# key-board.net
KiCad netlist of a schematic drawn in EAGLE
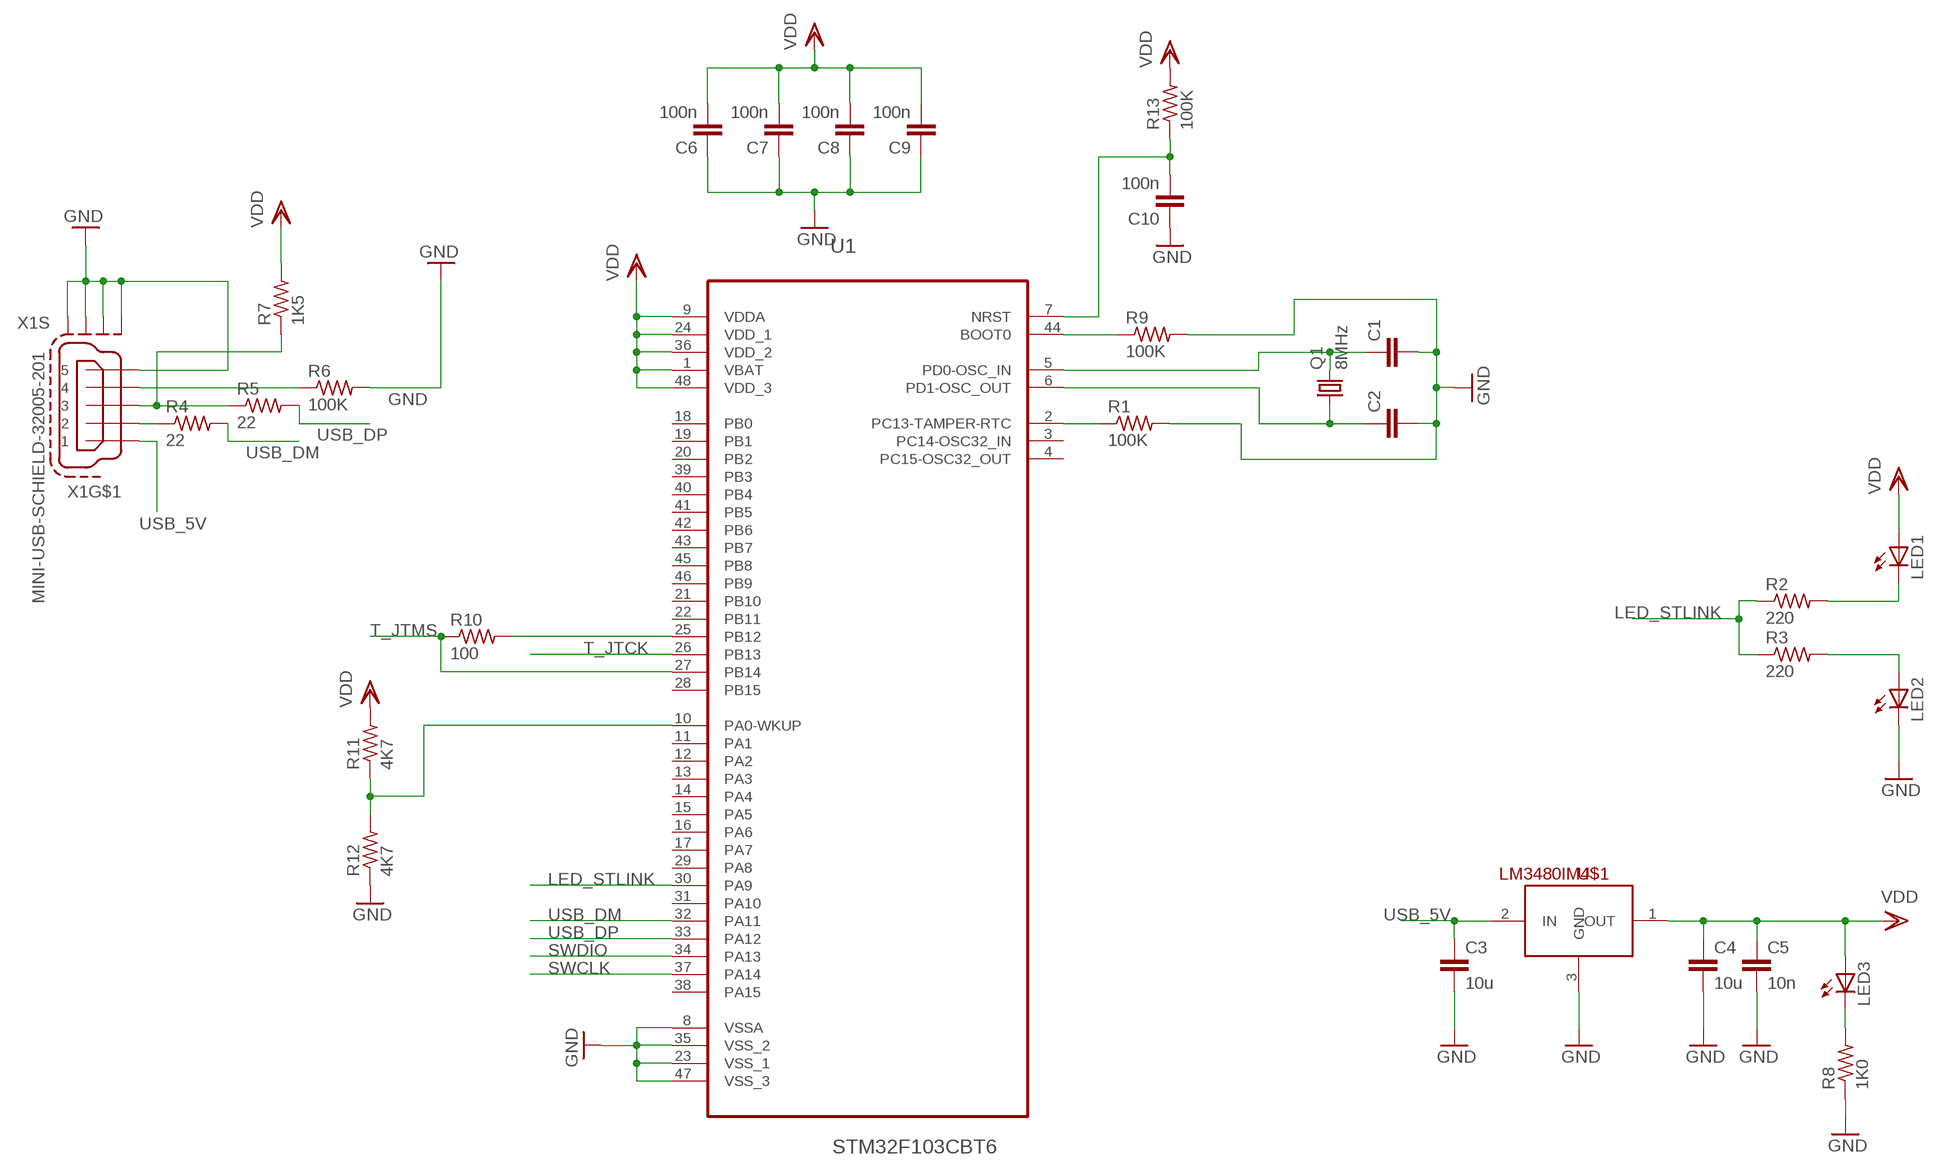
[diagram p0: schematic, sheet 1]

(export (version "E")
  (design (tool "Eeschema 10.0.6"))
  (components
    (comp (ref "C1")
      (value "C-EUC0402")
      (footprint "eagle-import:C0402")
      (libsource (lib "eagle-import") (part "C-EUC0402"))
    )
    (comp (ref "C2")
      (value "C-EUC0402")
      (footprint "eagle-import:C0402")
      (libsource (lib "eagle-import") (part "C-EUC0402"))
    )
    (comp (ref "C3")
      (value "10u")
      (footprint "eagle-import:C0805")
      (libsource (lib "eagle-import") (part "C-EUC0805"))
    )
    (comp (ref "C4")
      (value "10u")
      (footprint "eagle-import:C0805")
      (libsource (lib "eagle-import") (part "C-EUC0805"))
    )
    (comp (ref "C5")
      (value "10n")
      (footprint "eagle-import:C0402")
      (libsource (lib "eagle-import") (part "C-EUC0402"))
    )
    (comp (ref "C6")
      (value "100n")
      (footprint "eagle-import:C0402")
      (libsource (lib "eagle-import") (part "C-EUC0402"))
    )
    (comp (ref "C7")
      (value "100n")
      (footprint "eagle-import:C0402")
      (libsource (lib "eagle-import") (part "C-EUC0402"))
    )
    (comp (ref "C8")
      (value "100n")
      (footprint "eagle-import:C0402")
      (libsource (lib "eagle-import") (part "C-EUC0402"))
    )
    (comp (ref "C9")
      (value "100n")
      (footprint "eagle-import:C0402")
      (libsource (lib "eagle-import") (part "C-EUC0402"))
    )
    (comp (ref "C10")
      (value "100n")
      (footprint "eagle-import:C0402")
      (libsource (lib "eagle-import") (part "C-EUC0402"))
    )
    (comp (ref "LED1")
      (value "LEDCHIPLED-0603-TTW")
      (footprint "eagle-import:CHIPLED-0603-TTW")
      (libsource (lib "eagle-import") (part "LEDCHIPLED-0603-TTW"))
    )
    (comp (ref "LED2")
      (value "LEDCHIPLED-0603-TTW")
      (footprint "eagle-import:CHIPLED-0603-TTW")
      (libsource (lib "eagle-import") (part "LEDCHIPLED-0603-TTW"))
    )
    (comp (ref "LED3")
      (value "LEDCHIPLED-0603-TTW")
      (footprint "eagle-import:CHIPLED-0603-TTW")
      (libsource (lib "eagle-import") (part "LEDCHIPLED-0603-TTW"))
    )
    (comp (ref "Q1")
      (value "8MHz")
      (footprint "eagle-import:HC49U-V")
      (libsource (lib "eagle-import") (part "CRYSTALHC49U-V"))
    )
    (comp (ref "R1")
      (value "100K")
      (footprint "eagle-import:R0402")
      (libsource (lib "eagle-import") (part "R-US_R0402"))
    )
    (comp (ref "R2")
      (value "220")
      (footprint "eagle-import:R0402")
      (libsource (lib "eagle-import") (part "R-US_R0402"))
    )
    (comp (ref "R3")
      (value "220")
      (footprint "eagle-import:R0402")
      (libsource (lib "eagle-import") (part "R-US_R0402"))
    )
    (comp (ref "R4")
      (value "22")
      (footprint "eagle-import:R0402")
      (libsource (lib "eagle-import") (part "R-US_R0402"))
    )
    (comp (ref "R5")
      (value "22")
      (footprint "eagle-import:R0402")
      (libsource (lib "eagle-import") (part "R-US_R0402"))
    )
    (comp (ref "R6")
      (value "100K")
      (footprint "eagle-import:R0402")
      (libsource (lib "eagle-import") (part "R-US_R0402"))
    )
    (comp (ref "R7")
      (value "1K5")
      (footprint "eagle-import:R0402")
      (libsource (lib "eagle-import") (part "R-US_R0402"))
    )
    (comp (ref "R8")
      (value "1K0")
      (footprint "eagle-import:R0402")
      (libsource (lib "eagle-import") (part "R-US_R0402"))
    )
    (comp (ref "R9")
      (value "100K")
      (footprint "eagle-import:R0402")
      (libsource (lib "eagle-import") (part "R-US_R0402"))
    )
    (comp (ref "R10")
      (value "100")
      (footprint "eagle-import:R0402")
      (libsource (lib "eagle-import") (part "R-US_R0402"))
    )
    (comp (ref "R11")
      (value "4K7")
      (footprint "eagle-import:R0402")
      (libsource (lib "eagle-import") (part "R-US_R0402"))
    )
    (comp (ref "R12")
      (value "4K7")
      (footprint "eagle-import:R0402")
      (libsource (lib "eagle-import") (part "R-US_R0402"))
    )
    (comp (ref "R13")
      (value "100K")
      (footprint "eagle-import:R0402")
      (libsource (lib "eagle-import") (part "R-US_R0402"))
    )
    (comp (ref "U$1")
      (value "LM3480IM4")
      (footprint "eagle-import:SOT23-3")
      (libsource (lib "eagle-import") (part "LM3480IM4"))
    )
    (comp (ref "U1")
      (value "STM32F103CBT6")
      (footprint "eagle-import:QFP50P900X900X160-48N")
      (libsource (lib "eagle-import") (part "STM32F103CBT6"))
    )
    (comp (ref "X1")
      (value "MINI-USB-SCHIELD-32005-201")
      (footprint "eagle-import:32005-201")
      (libsource (lib "eagle-import") (part "MINI-USB-SCHIELD-32005-201"))
    )
  )
  (nets
    (net (code "1") (name "/LED_STLINK") (class "Default")
      (node (ref "R2") (pin "1") (pinfunction "1_1") (pintype "passive"))
      (node (ref "R3") (pin "1") (pinfunction "1_1") (pintype "passive"))
      (node (ref "U1") (pin "30") (pinfunction "PA9_30") (pintype "bidirectional"))
    )
    (net (code "2") (name "/SWCLK") (class "Default")
      (node (ref "U1") (pin "37") (pinfunction "PA14_37") (pintype "bidirectional"))
    )
    (net (code "3") (name "/SWDIO") (class "Default")
      (node (ref "U1") (pin "34") (pinfunction "PA13_34") (pintype "bidirectional"))
    )
    (net (code "4") (name "/T_JTCK") (class "Default")
      (node (ref "U1") (pin "26") (pinfunction "PB13_26") (pintype "bidirectional"))
    )
    (net (code "5") (name "/T_JTMS") (class "Default")
      (node (ref "R10") (pin "1") (pinfunction "1_1") (pintype "passive"))
      (node (ref "U1") (pin "27") (pinfunction "PB14_27") (pintype "bidirectional"))
    )
    (net (code "6") (name "/USB_5V") (class "Default")
      (node (ref "C3") (pin "1") (pinfunction "1_1") (pintype "passive"))
      (node (ref "U$1") (pin "2") (pinfunction "IN_2") (pintype "bidirectional"))
      (node (ref "X1") (pin "1") (pinfunction "1_1") (pintype "passive"))
    )
    (net (code "7") (name "/USB_DM") (class "Default")
      (node (ref "R4") (pin "2") (pinfunction "2_2") (pintype "passive"))
      (node (ref "U1") (pin "32") (pinfunction "PA11_32") (pintype "power_in"))
    )
    (net (code "8") (name "/USB_DP") (class "Default")
      (node (ref "R5") (pin "2") (pinfunction "2_2") (pintype "passive"))
      (node (ref "U1") (pin "33") (pinfunction "PA12_33") (pintype "bidirectional"))
    )
    (net (code "9") (name "GND") (class "Default")
      (node (ref "C1") (pin "2") (pinfunction "2_2") (pintype "passive"))
      (node (ref "C10") (pin "1") (pinfunction "1_1") (pintype "passive"))
      (node (ref "C2") (pin "2") (pinfunction "2_2") (pintype "passive"))
      (node (ref "C3") (pin "2") (pinfunction "2_2") (pintype "passive"))
      (node (ref "C4") (pin "2") (pinfunction "2_2") (pintype "passive"))
      (node (ref "C5") (pin "2") (pinfunction "2_2") (pintype "passive"))
      (node (ref "C6") (pin "1") (pinfunction "1_1") (pintype "passive"))
      (node (ref "C7") (pin "1") (pinfunction "1_1") (pintype "passive"))
      (node (ref "C8") (pin "1") (pinfunction "1_1") (pintype "passive"))
      (node (ref "C9") (pin "1") (pinfunction "1_1") (pintype "passive"))
      (node (ref "LED2") (pin "C@1") (pinfunction "C_C@1") (pintype "passive"))
      (node (ref "R1") (pin "2") (pinfunction "2_2") (pintype "passive"))
      (node (ref "R12") (pin "1") (pinfunction "1_1") (pintype "passive"))
      (node (ref "R6") (pin "2") (pinfunction "2_2") (pintype "passive"))
      (node (ref "R8") (pin "1") (pinfunction "1_1") (pintype "passive"))
      (node (ref "R9") (pin "2") (pinfunction "2_2") (pintype "passive"))
      (node (ref "U$1") (pin "3") (pinfunction "GND_3") (pintype "bidirectional"))
      (node (ref "U1") (pin "23") (pinfunction "VSS_1_23") (pintype "bidirectional"))
      (node (ref "U1") (pin "35") (pinfunction "VSS_2_35") (pintype "passive"))
      (node (ref "U1") (pin "47") (pinfunction "VSS_3_47") (pintype "passive"))
      (node (ref "U1") (pin "8") (pinfunction "VSSA_8") (pintype "passive"))
      (node (ref "X1") (pin "5") (pinfunction "5_5") (pintype "passive"))
      (node (ref "X1") (pin "M1") (pinfunction "S1_M1") (pintype "passive"))
      (node (ref "X1") (pin "M2") (pinfunction "S2_M2") (pintype "passive"))
      (node (ref "X1") (pin "M3") (pinfunction "S3_M3") (pintype "passive"))
      (node (ref "X1") (pin "M4") (pinfunction "S4_M4") (pintype "passive"))
    )
    (net (code "10") (name "Net-(LED1-C)") (class "Default")
      (node (ref "LED1") (pin "C@1") (pinfunction "C_C@1") (pintype "passive"))
      (node (ref "R2") (pin "2") (pinfunction "2_2") (pintype "passive"))
    )
    (net (code "11") (name "Net-(LED2-A)") (class "Default")
      (node (ref "LED2") (pin "A@1") (pinfunction "A_A@1") (pintype "passive"))
      (node (ref "R3") (pin "2") (pinfunction "2_2") (pintype "passive"))
    )
    (net (code "12") (name "Net-(LED3-C)") (class "Default")
      (node (ref "LED3") (pin "C@1") (pinfunction "C_C@1") (pintype "passive"))
      (node (ref "R8") (pin "2") (pinfunction "2_2") (pintype "passive"))
    )
    (net (code "13") (name "Net-(R4-Pad1)") (class "Default")
      (node (ref "R4") (pin "1") (pinfunction "1_1") (pintype "passive"))
      (node (ref "X1") (pin "2") (pinfunction "2_2") (pintype "passive"))
    )
    (net (code "14") (name "Net-(R5-Pad1)") (class "Default")
      (node (ref "R5") (pin "1") (pinfunction "1_1") (pintype "passive"))
      (node (ref "R7") (pin "1") (pinfunction "1_1") (pintype "passive"))
      (node (ref "X1") (pin "3") (pinfunction "3_3") (pintype "passive"))
    )
    (net (code "15") (name "Net-(R6-Pad1)") (class "Default")
      (node (ref "R6") (pin "1") (pinfunction "1_1") (pintype "passive"))
      (node (ref "X1") (pin "4") (pinfunction "4_4") (pintype "passive"))
    )
    (net (code "16") (name "Net-(U1-BOOT0)") (class "Default")
      (node (ref "R9") (pin "1") (pinfunction "1_1") (pintype "passive"))
      (node (ref "U1") (pin "44") (pinfunction "BOOT0_44") (pintype "bidirectional"))
    )
    (net (code "17") (name "Net-(U1-NRST)") (class "Default")
      (node (ref "C10") (pin "2") (pinfunction "2_2") (pintype "passive"))
      (node (ref "R13") (pin "1") (pinfunction "1_1") (pintype "passive"))
      (node (ref "U1") (pin "7") (pinfunction "NRST_7") (pintype "bidirectional"))
    )
    (net (code "18") (name "Net-(U1-PA0-WKUP)") (class "Default")
      (node (ref "R11") (pin "1") (pinfunction "1_1") (pintype "passive"))
      (node (ref "R12") (pin "2") (pinfunction "2_2") (pintype "passive"))
      (node (ref "U1") (pin "10") (pinfunction "PA0-WKUP_10") (pintype "bidirectional"))
    )
    (net (code "19") (name "Net-(U1-PB12)") (class "Default")
      (node (ref "R10") (pin "2") (pinfunction "2_2") (pintype "passive"))
      (node (ref "U1") (pin "25") (pinfunction "PB12_25") (pintype "bidirectional"))
    )
    (net (code "20") (name "Net-(U1-PC13-TAMPER-RTC)") (class "Default")
      (node (ref "R1") (pin "1") (pinfunction "1_1") (pintype "passive"))
      (node (ref "U1") (pin "2") (pinfunction "PC13-TAMPER-RTC_2") (pintype "bidirectional"))
    )
    (net (code "21") (name "Net-(U1-PD0-OSC_IN)") (class "Default")
      (node (ref "C1") (pin "1") (pinfunction "1_1") (pintype "passive"))
      (node (ref "Q1") (pin "2") (pinfunction "2_2") (pintype "passive"))
      (node (ref "U1") (pin "5") (pinfunction "PD0-OSC_IN_5") (pintype "bidirectional"))
    )
    (net (code "22") (name "Net-(U1-PD1-OSC_OUT)") (class "Default")
      (node (ref "C2") (pin "1") (pinfunction "1_1") (pintype "passive"))
      (node (ref "Q1") (pin "1") (pinfunction "1_1") (pintype "passive"))
      (node (ref "U1") (pin "6") (pinfunction "PD1-OSC_OUT_6") (pintype "bidirectional"))
    )
    (net (code "23") (name "VDD") (class "Default")
      (node (ref "C4") (pin "1") (pinfunction "1_1") (pintype "passive"))
      (node (ref "C5") (pin "1") (pinfunction "1_1") (pintype "passive"))
      (node (ref "C6") (pin "2") (pinfunction "2_2") (pintype "passive"))
      (node (ref "C7") (pin "2") (pinfunction "2_2") (pintype "passive"))
      (node (ref "C8") (pin "2") (pinfunction "2_2") (pintype "passive"))
      (node (ref "C9") (pin "2") (pinfunction "2_2") (pintype "passive"))
      (node (ref "LED1") (pin "A@1") (pinfunction "A_A@1") (pintype "passive"))
      (node (ref "LED3") (pin "A@1") (pinfunction "A_A@1") (pintype "passive"))
      (node (ref "R11") (pin "2") (pinfunction "2_2") (pintype "passive"))
      (node (ref "R13") (pin "2") (pinfunction "2_2") (pintype "passive"))
      (node (ref "R7") (pin "2") (pinfunction "2_2") (pintype "passive"))
      (node (ref "U$1") (pin "1") (pinfunction "OUT_1") (pintype "bidirectional"))
      (node (ref "U1") (pin "1") (pinfunction "VBAT_1") (pintype "input"))
      (node (ref "U1") (pin "24") (pinfunction "VDD_1_24") (pintype "bidirectional"))
      (node (ref "U1") (pin "36") (pinfunction "VDD_2_36") (pintype "power_in"))
      (node (ref "U1") (pin "48") (pinfunction "VDD_3_48") (pintype "power_in"))
      (node (ref "U1") (pin "9") (pinfunction "VDDA_9") (pintype "power_in"))
    )
    (net (code "24") (name "unconnected-(U1-PA1-Pad11)") (class "Default")
      (node (ref "U1") (pin "11") (pinfunction "PA1_11") (pintype "bidirectional"))
    )
    (net (code "25") (name "unconnected-(U1-PA2-Pad12)") (class "Default")
      (node (ref "U1") (pin "12") (pinfunction "PA2_12") (pintype "bidirectional"))
    )
    (net (code "26") (name "unconnected-(U1-PA3-Pad13)") (class "Default")
      (node (ref "U1") (pin "13") (pinfunction "PA3_13") (pintype "bidirectional"))
    )
    (net (code "27") (name "unconnected-(U1-PA4-Pad14)") (class "Default")
      (node (ref "U1") (pin "14") (pinfunction "PA4_14") (pintype "bidirectional"))
    )
    (net (code "28") (name "unconnected-(U1-PA5-Pad15)") (class "Default")
      (node (ref "U1") (pin "15") (pinfunction "PA5_15") (pintype "bidirectional"))
    )
    (net (code "29") (name "unconnected-(U1-PA6-Pad16)") (class "Default")
      (node (ref "U1") (pin "16") (pinfunction "PA6_16") (pintype "bidirectional"))
    )
    (net (code "30") (name "unconnected-(U1-PA7-Pad17)") (class "Default")
      (node (ref "U1") (pin "17") (pinfunction "PA7_17") (pintype "bidirectional"))
    )
    (net (code "31") (name "unconnected-(U1-PA8-Pad29)") (class "Default")
      (node (ref "U1") (pin "29") (pinfunction "PA8_29") (pintype "bidirectional"))
    )
    (net (code "32") (name "unconnected-(U1-PA10-Pad31)") (class "Default")
      (node (ref "U1") (pin "31") (pinfunction "PA10_31") (pintype "bidirectional"))
    )
    (net (code "33") (name "unconnected-(U1-PA15-Pad38)") (class "Default")
      (node (ref "U1") (pin "38") (pinfunction "PA15_38") (pintype "bidirectional"))
    )
    (net (code "34") (name "unconnected-(U1-PB0-Pad18)") (class "Default")
      (node (ref "U1") (pin "18") (pinfunction "PB0_18") (pintype "bidirectional"))
    )
    (net (code "35") (name "unconnected-(U1-PB1-Pad19)") (class "Default")
      (node (ref "U1") (pin "19") (pinfunction "PB1_19") (pintype "bidirectional"))
    )
    (net (code "36") (name "unconnected-(U1-PB2-Pad20)") (class "Default")
      (node (ref "U1") (pin "20") (pinfunction "PB2_20") (pintype "bidirectional"))
    )
    (net (code "37") (name "unconnected-(U1-PB3-Pad39)") (class "Default")
      (node (ref "U1") (pin "39") (pinfunction "PB3_39") (pintype "bidirectional"))
    )
    (net (code "38") (name "unconnected-(U1-PB4-Pad40)") (class "Default")
      (node (ref "U1") (pin "40") (pinfunction "PB4_40") (pintype "bidirectional"))
    )
    (net (code "39") (name "unconnected-(U1-PB5-Pad41)") (class "Default")
      (node (ref "U1") (pin "41") (pinfunction "PB5_41") (pintype "bidirectional"))
    )
    (net (code "40") (name "unconnected-(U1-PB6-Pad42)") (class "Default")
      (node (ref "U1") (pin "42") (pinfunction "PB6_42") (pintype "bidirectional"))
    )
    (net (code "41") (name "unconnected-(U1-PB7-Pad43)") (class "Default")
      (node (ref "U1") (pin "43") (pinfunction "PB7_43") (pintype "bidirectional"))
    )
    (net (code "42") (name "unconnected-(U1-PB8-Pad45)") (class "Default")
      (node (ref "U1") (pin "45") (pinfunction "PB8_45") (pintype "bidirectional"))
    )
    (net (code "43") (name "unconnected-(U1-PB9-Pad46)") (class "Default")
      (node (ref "U1") (pin "46") (pinfunction "PB9_46") (pintype "bidirectional"))
    )
    (net (code "44") (name "unconnected-(U1-PB10-Pad21)") (class "Default")
      (node (ref "U1") (pin "21") (pinfunction "PB10_21") (pintype "bidirectional"))
    )
    (net (code "45") (name "unconnected-(U1-PB11-Pad22)") (class "Default")
      (node (ref "U1") (pin "22") (pinfunction "PB11_22") (pintype "bidirectional"))
    )
    (net (code "46") (name "unconnected-(U1-PB15-Pad28)") (class "Default")
      (node (ref "U1") (pin "28") (pinfunction "PB15_28") (pintype "bidirectional"))
    )
    (net (code "47") (name "unconnected-(U1-PC14-OSC32_IN-Pad3)") (class "Default")
      (node (ref "U1") (pin "3") (pinfunction "PC14-OSC32_IN_3") (pintype "bidirectional"))
    )
    (net (code "48") (name "unconnected-(U1-PC15-OSC32_OUT-Pad4)") (class "Default")
      (node (ref "U1") (pin "4") (pinfunction "PC15-OSC32_OUT_4") (pintype "bidirectional"))
    )
  )
)
